# control_100.net
KiCad netlist of a schematic drawn in EAGLE
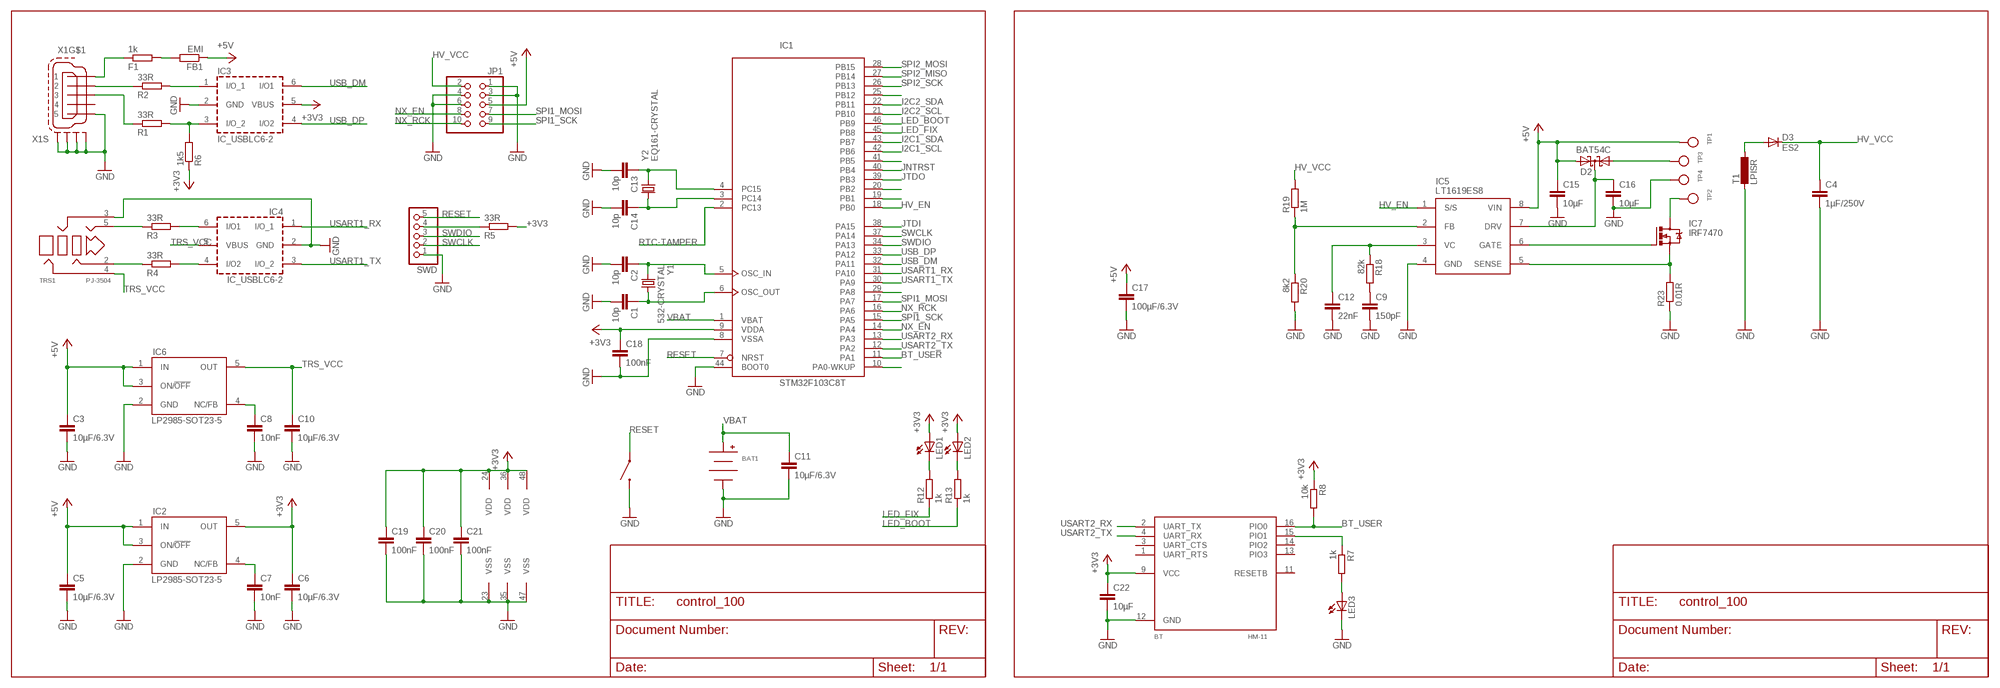
[diagram p0: schematic, sheet 1]

(export (version "E")
  (design (tool "Eeschema 10.0.6"))
  (components
    (comp (ref "BAT1")
      (value "CR1220-HOLDER")
      (footprint "eagle-import:HARWIN-CR1220")
      (libsource (lib "eagle-import") (part "CR1220-HOLDER"))
    )
    (comp (ref "BT")
      (value "HM-11")
      (footprint "eagle-import:HM-11")
      (libsource (lib "eagle-import") (part "HM-11"))
    )
    (comp (ref "C1")
      (value "10p")
      (footprint "eagle-import:C0603")
      (libsource (lib "eagle-import") (part "C-EUC0603"))
    )
    (comp (ref "C2")
      (value "10p")
      (footprint "eagle-import:C0603")
      (libsource (lib "eagle-import") (part "C-EUC0603"))
    )
    (comp (ref "C3")
      (value "10µF/6.3V")
      (footprint "eagle-import:C0603")
      (libsource (lib "eagle-import") (part "C-EUC0603"))
    )
    (comp (ref "C4")
      (value "1µF/250V")
      (footprint "eagle-import:C2220K")
      (libsource (lib "eagle-import") (part "C-EUC2220K"))
    )
    (comp (ref "C5")
      (value "10µF/6.3V")
      (footprint "eagle-import:C0603")
      (libsource (lib "eagle-import") (part "C-EUC0603"))
    )
    (comp (ref "C6")
      (value "10µF/6.3V")
      (footprint "eagle-import:C0603")
      (libsource (lib "eagle-import") (part "C-EUC0603"))
    )
    (comp (ref "C7")
      (value "10nF")
      (footprint "eagle-import:C0603")
      (libsource (lib "eagle-import") (part "C-EUC0603"))
    )
    (comp (ref "C8")
      (value "10nF")
      (footprint "eagle-import:C0603")
      (libsource (lib "eagle-import") (part "C-EUC0603"))
    )
    (comp (ref "C9")
      (value "150pF")
      (footprint "eagle-import:C0603")
      (libsource (lib "eagle-import") (part "C-EUC0603"))
    )
    (comp (ref "C10")
      (value "10µF/6.3V")
      (footprint "eagle-import:C0603")
      (libsource (lib "eagle-import") (part "C-EUC0603"))
    )
    (comp (ref "C11")
      (value "10µF/6.3V")
      (footprint "eagle-import:C0603")
      (libsource (lib "eagle-import") (part "C-EUC0603"))
    )
    (comp (ref "C12")
      (value "22nF")
      (footprint "eagle-import:C0603")
      (libsource (lib "eagle-import") (part "C-EUC0603"))
    )
    (comp (ref "C13")
      (value "10p")
      (footprint "eagle-import:C0603")
      (libsource (lib "eagle-import") (part "C-EUC0603"))
    )
    (comp (ref "C14")
      (value "10p")
      (footprint "eagle-import:C0603")
      (libsource (lib "eagle-import") (part "C-EUC0603"))
    )
    (comp (ref "C15")
      (value "10µF")
      (footprint "eagle-import:C0603")
      (libsource (lib "eagle-import") (part "C-EUC0603"))
    )
    (comp (ref "C16")
      (value "10µF")
      (footprint "eagle-import:C0603")
      (libsource (lib "eagle-import") (part "C-EUC0603"))
    )
    (comp (ref "C17")
      (value "100µF/6.3V")
      (footprint "eagle-import:C1210")
      (libsource (lib "eagle-import") (part "C-EUC1210"))
    )
    (comp (ref "C18")
      (value "100nF")
      (footprint "eagle-import:C0603")
      (libsource (lib "eagle-import") (part "C-EUC0603"))
    )
    (comp (ref "C19")
      (value "100nF")
      (footprint "eagle-import:C0603")
      (libsource (lib "eagle-import") (part "C-EUC0603"))
    )
    (comp (ref "C20")
      (value "100nF")
      (footprint "eagle-import:C0603")
      (libsource (lib "eagle-import") (part "C-EUC0603"))
    )
    (comp (ref "C21")
      (value "100nF")
      (footprint "eagle-import:C0603")
      (libsource (lib "eagle-import") (part "C-EUC0603"))
    )
    (comp (ref "C22")
      (value "10µF")
      (footprint "eagle-import:C0603")
      (libsource (lib "eagle-import") (part "C-EUC0603"))
    )
    (comp (ref "D2")
      (value "BAT54C")
      (footprint "eagle-import:SOT23")
      (libsource (lib "eagle-import") (part "BAT54C"))
    )
    (comp (ref "D3")
      (value "ES2")
      (footprint "eagle-import:DO-214AA")
      (libsource (lib "eagle-import") (part "ES2"))
    )
    (comp (ref "F1")
      (value "1k")
      (footprint "eagle-import:R0603")
      (libsource (lib "eagle-import") (part "R-EU_R0603"))
    )
    (comp (ref "FB1")
      (value "EMI")
      (footprint "eagle-import:R0603")
      (libsource (lib "eagle-import") (part "R-EU_R0603"))
    )
    (comp (ref "IC1")
      (value "STM32F103C8T")
      (footprint "eagle-import:LQFP48")
      (libsource (lib "eagle-import") (part "STM32F103CT8"))
    )
    (comp (ref "IC2")
      (value "LP2985-SOT23-5")
      (footprint "eagle-import:SOT23-5")
      (libsource (lib "eagle-import") (part "LP2985-SOT23-5"))
    )
    (comp (ref "IC3")
      (value "IC_USBLC6-2")
      (footprint "eagle-import:SOT-23-6L")
      (libsource (lib "eagle-import") (part "IC_USBLC6-2"))
    )
    (comp (ref "IC4")
      (value "IC_USBLC6-2")
      (footprint "eagle-import:SOT-23-6L")
      (libsource (lib "eagle-import") (part "IC_USBLC6-2"))
    )
    (comp (ref "IC5")
      (value "LT1619ES8")
      (footprint "eagle-import:SO8")
      (libsource (lib "eagle-import") (part "LT1619ES8"))
    )
    (comp (ref "IC6")
      (value "LP2985-SOT23-5")
      (footprint "eagle-import:SOT23-5")
      (libsource (lib "eagle-import") (part "LP2985-SOT23-5"))
    )
    (comp (ref "IC7")
      (value "IRF7470")
      (footprint "eagle-import:SO8")
      (libsource (lib "eagle-import") (part "IRF7470"))
    )
    (comp (ref "ISP")
      (value "TACT-SWITCH-40-40")
      (footprint "eagle-import:40-40")
      (libsource (lib "eagle-import") (part "TACT-SWITCH-40-40"))
    )
    (comp (ref "JP1")
      (value "PINHD-2X5_2.54-SMD")
      (footprint "eagle-import:2X05SMD")
      (libsource (lib "eagle-import") (part "PINHD-2X5_2.54-SMD"))
    )
    (comp (ref "LED1")
      (value "LEDCHIP-LED0603")
      (footprint "eagle-import:CHIP-LED0603")
      (libsource (lib "eagle-import") (part "LEDCHIP-LED0603"))
    )
    (comp (ref "LED2")
      (value "LEDCHIP-LED0603")
      (footprint "eagle-import:CHIP-LED0603")
      (libsource (lib "eagle-import") (part "LEDCHIP-LED0603"))
    )
    (comp (ref "LED3")
      (value "LEDCHIP-LED0603")
      (footprint "eagle-import:CHIP-LED0603")
      (libsource (lib "eagle-import") (part "LEDCHIP-LED0603"))
    )
    (comp (ref "R1")
      (value "33R")
      (footprint "eagle-import:R0603")
      (libsource (lib "eagle-import") (part "R-EU_R0603"))
    )
    (comp (ref "R2")
      (value "33R")
      (footprint "eagle-import:R0603")
      (libsource (lib "eagle-import") (part "R-EU_R0603"))
    )
    (comp (ref "R3")
      (value "33R")
      (footprint "eagle-import:R0603")
      (libsource (lib "eagle-import") (part "R-EU_R0603"))
    )
    (comp (ref "R4")
      (value "33R")
      (footprint "eagle-import:R0603")
      (libsource (lib "eagle-import") (part "R-EU_R0603"))
    )
    (comp (ref "R5")
      (value "33R")
      (footprint "eagle-import:R0603")
      (libsource (lib "eagle-import") (part "R-EU_R0603"))
    )
    (comp (ref "R6")
      (value "1k5")
      (footprint "eagle-import:R0603")
      (libsource (lib "eagle-import") (part "R-EU_R0603"))
    )
    (comp (ref "R7")
      (value "1k")
      (footprint "eagle-import:R0603")
      (libsource (lib "eagle-import") (part "R-EU_R0603"))
    )
    (comp (ref "R8")
      (value "10k")
      (footprint "eagle-import:R0603")
      (libsource (lib "eagle-import") (part "R-EU_R0603"))
    )
    (comp (ref "R12")
      (value "1k")
      (footprint "eagle-import:R0603")
      (libsource (lib "eagle-import") (part "R-EU_R0603"))
    )
    (comp (ref "R13")
      (value "1k")
      (footprint "eagle-import:R0603")
      (libsource (lib "eagle-import") (part "R-EU_R0603"))
    )
    (comp (ref "R18")
      (value "82k")
      (footprint "eagle-import:R0603")
      (libsource (lib "eagle-import") (part "R-EU_R0603"))
    )
    (comp (ref "R19")
      (value "1M")
      (footprint "eagle-import:M1206")
      (libsource (lib "eagle-import") (part "R-EU_M1206"))
    )
    (comp (ref "R20")
      (value "8k2")
      (footprint "eagle-import:R0603")
      (libsource (lib "eagle-import") (part "R-EU_R0603"))
    )
    (comp (ref "R23")
      (value "0.01R")
      (footprint "eagle-import:R1206")
      (libsource (lib "eagle-import") (part "R-EU_R1206"))
    )
    (comp (ref "SWD")
      (value "HEADER-1X5ROUND")
      (footprint "eagle-import:1X05_ROUND")
      (libsource (lib "eagle-import") (part "HEADER-1X5ROUND"))
    )
    (comp (ref "T1")
      (value "LPISR")
      (footprint "eagle-import:PISR")
      (libsource (lib "eagle-import") (part "LPISR"))
    )
    (comp (ref "TP1")
      (value "TESTPOINTROUND2MM")
      (footprint "eagle-import:TESTPOINT_ROUND_2MM")
      (libsource (lib "eagle-import") (part "TESTPOINTROUND2MM"))
    )
    (comp (ref "TP2")
      (value "TESTPOINTROUND2MM")
      (footprint "eagle-import:TESTPOINT_ROUND_2MM")
      (libsource (lib "eagle-import") (part "TESTPOINTROUND2MM"))
    )
    (comp (ref "TP3")
      (value "TESTPOINTROUND2MM")
      (footprint "eagle-import:TESTPOINT_ROUND_2MM")
      (libsource (lib "eagle-import") (part "TESTPOINTROUND2MM"))
    )
    (comp (ref "TP4")
      (value "TESTPOINTROUND2MM")
      (footprint "eagle-import:TESTPOINT_ROUND_2MM")
      (libsource (lib "eagle-import") (part "TESTPOINTROUND2MM"))
    )
    (comp (ref "TRS1")
      (value "PJ-3504")
      (footprint "eagle-import:YD-PJ-3504")
      (libsource (lib "eagle-import") (part "PJ-3504"))
    )
    (comp (ref "X1")
      (value "MINI-USB-SCHIELD-32005-201")
      (footprint "eagle-import:32005-201")
      (libsource (lib "eagle-import") (part "MINI-USB-SCHIELD-32005-201"))
    )
    (comp (ref "Y1")
      (value "532-CRYSTAL")
      (footprint "eagle-import:2PIN50X32")
      (libsource (lib "eagle-import") (part "532-CRYSTAL"))
    )
    (comp (ref "Y2")
      (value "EQ161-CRYSTAL")
      (footprint "eagle-import:EQ161")
      (libsource (lib "eagle-import") (part "EQ161-CRYSTAL"))
    )
  )
  (nets
    (net (code "1") (name "+3V3") (class "Default")
      (node (ref "BT") (pin "9") (pinfunction "VCC_9") (pintype "bidirectional"))
      (node (ref "C18") (pin "1") (pinfunction "1_1") (pintype "passive"))
      (node (ref "C19") (pin "1") (pinfunction "1_1") (pintype "passive"))
      (node (ref "C20") (pin "1") (pinfunction "1_1") (pintype "passive"))
      (node (ref "C21") (pin "1") (pinfunction "1_1") (pintype "passive"))
      (node (ref "C22") (pin "1") (pinfunction "1_1") (pintype "passive"))
      (node (ref "C6") (pin "1") (pinfunction "1_1") (pintype "passive"))
      (node (ref "IC1") (pin "24") (pinfunction "VDD_24") (pintype "power_in"))
      (node (ref "IC1") (pin "36") (pinfunction "VDD_36") (pintype "power_in"))
      (node (ref "IC1") (pin "48") (pinfunction "VDD_48") (pintype "power_in"))
      (node (ref "IC1") (pin "9") (pinfunction "VDDA_9") (pintype "power_in"))
      (node (ref "IC2") (pin "5") (pinfunction "OUT_5") (pintype "bidirectional"))
      (node (ref "IC3") (pin "5") (pinfunction "VBUS_5") (pintype "bidirectional"))
      (node (ref "LED1") (pin "A") (pinfunction "A_A") (pintype "passive"))
      (node (ref "LED2") (pin "A") (pinfunction "A_A") (pintype "passive"))
      (node (ref "R5") (pin "2") (pinfunction "2_2") (pintype "passive"))
      (node (ref "R6") (pin "1") (pinfunction "1_1") (pintype "passive"))
      (node (ref "R8") (pin "1") (pinfunction "1_1") (pintype "passive"))
    )
    (net (code "2") (name "+5V") (class "Default")
      (node (ref "C15") (pin "1") (pinfunction "1_1") (pintype "passive"))
      (node (ref "C17") (pin "1") (pinfunction "1_1") (pintype "passive"))
      (node (ref "C3") (pin "1") (pinfunction "1_1") (pintype "passive"))
      (node (ref "C5") (pin "1") (pinfunction "1_1") (pintype "passive"))
      (node (ref "D2") (pin "2") (pinfunction "A2_2") (pintype "passive"))
      (node (ref "FB1") (pin "1") (pinfunction "1_1") (pintype "passive"))
      (node (ref "IC2") (pin "1") (pinfunction "IN_1") (pintype "bidirectional"))
      (node (ref "IC2") (pin "3") (pinfunction "ON/~{OFF}_3") (pintype "bidirectional"))
      (node (ref "IC5") (pin "8") (pinfunction "VIN_8") (pintype "bidirectional"))
      (node (ref "IC6") (pin "1") (pinfunction "IN_1") (pintype "bidirectional"))
      (node (ref "IC6") (pin "3") (pinfunction "ON/~{OFF}_3") (pintype "bidirectional"))
      (node (ref "JP1") (pin "5") (pinfunction "5_5") (pintype "passive"))
      (node (ref "TP1") (pin "P$1") (pinfunction "P$1_P$1") (pintype "bidirectional"))
    )
    (net (code "3") (name "/BT_USER") (class "Default")
      (node (ref "BT") (pin "16") (pinfunction "PIO0_16") (pintype "bidirectional"))
      (node (ref "IC1") (pin "11") (pinfunction "PA1_11") (pintype "bidirectional"))
      (node (ref "R8") (pin "2") (pinfunction "2_2") (pintype "passive"))
    )
    (net (code "4") (name "/HV_EN") (class "Default")
      (node (ref "IC1") (pin "18") (pinfunction "PB0_18") (pintype "bidirectional"))
      (node (ref "IC5") (pin "1") (pinfunction "S/S_1") (pintype "bidirectional"))
    )
    (net (code "5") (name "/HV_VCC") (class "Default")
      (node (ref "C4") (pin "1") (pinfunction "1_1") (pintype "passive"))
      (node (ref "D3") (pin "C") (pinfunction "C_C") (pintype "passive"))
      (node (ref "JP1") (pin "2") (pinfunction "2_2") (pintype "passive"))
      (node (ref "R19") (pin "2") (pinfunction "2_2") (pintype "passive"))
    )
    (net (code "6") (name "/I2C1_SCL") (class "Default")
      (node (ref "IC1") (pin "42") (pinfunction "PB6_42") (pintype "bidirectional"))
    )
    (net (code "7") (name "/I2C1_SDA") (class "Default")
      (node (ref "IC1") (pin "43") (pinfunction "PB7_43") (pintype "bidirectional"))
    )
    (net (code "8") (name "/I2C2_SCL") (class "Default")
      (node (ref "IC1") (pin "21") (pinfunction "PB10_21") (pintype "bidirectional"))
    )
    (net (code "9") (name "/I2C2_SDA") (class "Default")
      (node (ref "IC1") (pin "22") (pinfunction "PB11_22") (pintype "bidirectional"))
    )
    (net (code "10") (name "/JNTRST") (class "Default")
      (node (ref "IC1") (pin "40") (pinfunction "PB4_40") (pintype "bidirectional"))
    )
    (net (code "11") (name "/JTDI") (class "Default")
      (node (ref "IC1") (pin "38") (pinfunction "PA15_38") (pintype "bidirectional"))
    )
    (net (code "12") (name "/JTDO") (class "Default")
      (node (ref "IC1") (pin "39") (pinfunction "PB3_39") (pintype "bidirectional"))
    )
    (net (code "13") (name "/LED_BOOT") (class "Default")
      (node (ref "IC1") (pin "46") (pinfunction "PB9_46") (pintype "bidirectional"))
      (node (ref "R13") (pin "1") (pinfunction "1_1") (pintype "passive"))
    )
    (net (code "14") (name "/LED_FIX") (class "Default")
      (node (ref "IC1") (pin "45") (pinfunction "PB8_45") (pintype "bidirectional"))
      (node (ref "R12") (pin "1") (pinfunction "1_1") (pintype "passive"))
    )
    (net (code "15") (name "/NX_EN") (class "Default")
      (node (ref "IC1") (pin "14") (pinfunction "PA4_14") (pintype "bidirectional"))
      (node (ref "JP1") (pin "8") (pinfunction "8_8") (pintype "passive"))
    )
    (net (code "16") (name "/NX_RCK") (class "Default")
      (node (ref "IC1") (pin "16") (pinfunction "PA6_16") (pintype "bidirectional"))
      (node (ref "JP1") (pin "10") (pinfunction "10_10") (pintype "passive"))
    )
    (net (code "17") (name "/RESET") (class "Default")
      (node (ref "IC1") (pin "7") (pinfunction "NRST_7") (pintype "bidirectional"))
      (node (ref "ISP") (pin "3") (pinfunction "P$2_3") (pintype "bidirectional"))
      (node (ref "ISP") (pin "4") (pinfunction "P$2_4") (pintype "bidirectional"))
      (node (ref "SWD") (pin "5") (pinfunction "5_5") (pintype "passive"))
    )
    (net (code "18") (name "/RTC-TAMPER") (class "Default")
      (node (ref "IC1") (pin "2") (pinfunction "PC13_2") (pintype "bidirectional"))
    )
    (net (code "19") (name "/SPI1_MOSI") (class "Default")
      (node (ref "IC1") (pin "17") (pinfunction "PA7_17") (pintype "bidirectional"))
      (node (ref "JP1") (pin "7") (pinfunction "7_7") (pintype "passive"))
    )
    (net (code "20") (name "/SPI1_SCK") (class "Default")
      (node (ref "IC1") (pin "15") (pinfunction "PA5_15") (pintype "bidirectional"))
      (node (ref "JP1") (pin "9") (pinfunction "9_9") (pintype "passive"))
    )
    (net (code "21") (name "/SPI2_MISO") (class "Default")
      (node (ref "IC1") (pin "27") (pinfunction "PB14_27") (pintype "bidirectional"))
    )
    (net (code "22") (name "/SPI2_MOSI") (class "Default")
      (node (ref "IC1") (pin "28") (pinfunction "PB15_28") (pintype "bidirectional"))
    )
    (net (code "23") (name "/SPI2_SCK") (class "Default")
      (node (ref "IC1") (pin "26") (pinfunction "PB13_26") (pintype "bidirectional"))
    )
    (net (code "24") (name "/SWCLK") (class "Default")
      (node (ref "IC1") (pin "37") (pinfunction "PA14_37") (pintype "bidirectional"))
      (node (ref "SWD") (pin "2") (pinfunction "2_2") (pintype "passive"))
    )
    (net (code "25") (name "/SWDIO") (class "Default")
      (node (ref "IC1") (pin "34") (pinfunction "PA13_34") (pintype "bidirectional"))
      (node (ref "SWD") (pin "3") (pinfunction "3_3") (pintype "passive"))
    )
    (net (code "26") (name "/TRS_VCC") (class "Default")
      (node (ref "C10") (pin "1") (pinfunction "1_1") (pintype "passive"))
      (node (ref "IC4") (pin "5") (pinfunction "VBUS_5") (pintype "bidirectional"))
      (node (ref "IC6") (pin "5") (pinfunction "OUT_5") (pintype "bidirectional"))
      (node (ref "TRS1") (pin "4") (pinfunction "4_4") (pintype "bidirectional"))
    )
    (net (code "27") (name "/USART1_RX") (class "Default")
      (node (ref "IC1") (pin "31") (pinfunction "PA10_31") (pintype "bidirectional"))
      (node (ref "IC4") (pin "1") (pinfunction "I/O_1_1") (pintype "bidirectional"))
    )
    (net (code "28") (name "/USART1_TX") (class "Default")
      (node (ref "IC1") (pin "30") (pinfunction "PA9_30") (pintype "bidirectional"))
      (node (ref "IC4") (pin "3") (pinfunction "I/O_2_3") (pintype "bidirectional"))
    )
    (net (code "29") (name "/USART2_RX") (class "Default")
      (node (ref "BT") (pin "2") (pinfunction "UART_TX_2") (pintype "bidirectional"))
      (node (ref "IC1") (pin "13") (pinfunction "PA3_13") (pintype "bidirectional"))
    )
    (net (code "30") (name "/USART2_TX") (class "Default")
      (node (ref "BT") (pin "4") (pinfunction "UART_RX_4") (pintype "bidirectional"))
      (node (ref "IC1") (pin "12") (pinfunction "PA2_12") (pintype "bidirectional"))
    )
    (net (code "31") (name "/USB_DM") (class "Default")
      (node (ref "IC1") (pin "32") (pinfunction "PA11_32") (pintype "bidirectional"))
      (node (ref "IC3") (pin "6") (pinfunction "I/O1_6") (pintype "bidirectional"))
    )
    (net (code "32") (name "/USB_DP") (class "Default")
      (node (ref "IC1") (pin "33") (pinfunction "PA12_33") (pintype "bidirectional"))
      (node (ref "IC3") (pin "4") (pinfunction "I/O2_4") (pintype "bidirectional"))
    )
    (net (code "33") (name "/VBAT") (class "Default")
      (node (ref "BAT1") (pin "POS") (pinfunction "POS_POS") (pintype "bidirectional"))
      (node (ref "C11") (pin "1") (pinfunction "1_1") (pintype "passive"))
      (node (ref "IC1") (pin "1") (pinfunction "VBAT_1") (pintype "power_in"))
    )
    (net (code "34") (name "GND") (class "Default")
      (node (ref "BAT1") (pin "NEG") (pinfunction "NEG_NEG") (pintype "bidirectional"))
      (node (ref "BT") (pin "12") (pinfunction "GND_12") (pintype "bidirectional"))
      (node (ref "C1") (pin "2") (pinfunction "2_2") (pintype "passive"))
      (node (ref "C10") (pin "2") (pinfunction "2_2") (pintype "passive"))
      (node (ref "C11") (pin "2") (pinfunction "2_2") (pintype "passive"))
      (node (ref "C12") (pin "2") (pinfunction "2_2") (pintype "passive"))
      (node (ref "C13") (pin "2") (pinfunction "2_2") (pintype "passive"))
      (node (ref "C14") (pin "2") (pinfunction "2_2") (pintype "passive"))
      (node (ref "C15") (pin "2") (pinfunction "2_2") (pintype "passive"))
      (node (ref "C16") (pin "2") (pinfunction "2_2") (pintype "passive"))
      (node (ref "C17") (pin "2") (pinfunction "2_2") (pintype "passive"))
      (node (ref "C18") (pin "2") (pinfunction "2_2") (pintype "passive"))
      (node (ref "C19") (pin "2") (pinfunction "2_2") (pintype "passive"))
      (node (ref "C2") (pin "2") (pinfunction "2_2") (pintype "passive"))
      (node (ref "C20") (pin "2") (pinfunction "2_2") (pintype "passive"))
      (node (ref "C21") (pin "2") (pinfunction "2_2") (pintype "passive"))
      (node (ref "C22") (pin "2") (pinfunction "2_2") (pintype "passive"))
      (node (ref "C3") (pin "2") (pinfunction "2_2") (pintype "passive"))
      (node (ref "C4") (pin "2") (pinfunction "2_2") (pintype "passive"))
      (node (ref "C5") (pin "2") (pinfunction "2_2") (pintype "passive"))
      (node (ref "C6") (pin "2") (pinfunction "2_2") (pintype "passive"))
      (node (ref "C7") (pin "2") (pinfunction "2_2") (pintype "passive"))
      (node (ref "C8") (pin "2") (pinfunction "2_2") (pintype "passive"))
      (node (ref "C9") (pin "2") (pinfunction "2_2") (pintype "passive"))
      (node (ref "IC1") (pin "23") (pinfunction "VSS_23") (pintype "power_in"))
      (node (ref "IC1") (pin "35") (pinfunction "VSS_35") (pintype "power_in"))
      (node (ref "IC1") (pin "44") (pinfunction "BOOT0_44") (pintype "input"))
      (node (ref "IC1") (pin "47") (pinfunction "VSS_47") (pintype "power_in"))
      (node (ref "IC1") (pin "8") (pinfunction "VSSA_8") (pintype "power_in"))
      (node (ref "IC2") (pin "2") (pinfunction "GND_2") (pintype "bidirectional"))
      (node (ref "IC3") (pin "2") (pinfunction "GND_2") (pintype "bidirectional"))
      (node (ref "IC4") (pin "2") (pinfunction "GND_2") (pintype "bidirectional"))
      (node (ref "IC5") (pin "4") (pinfunction "GND_4") (pintype "bidirectional"))
      (node (ref "IC6") (pin "2") (pinfunction "GND_2") (pintype "bidirectional"))
      (node (ref "ISP") (pin "1") (pinfunction "P$1_1") (pintype "bidirectional"))
      (node (ref "ISP") (pin "2") (pinfunction "P$1_2") (pintype "bidirectional"))
      (node (ref "JP1") (pin "1") (pinfunction "1_1") (pintype "passive"))
      (node (ref "JP1") (pin "3") (pinfunction "3_3") (pintype "passive"))
      (node (ref "JP1") (pin "4") (pinfunction "4_4") (pintype "passive"))
      (node (ref "JP1") (pin "6") (pinfunction "6_6") (pintype "passive"))
      (node (ref "LED3") (pin "C") (pinfunction "C_C") (pintype "passive"))
      (node (ref "R20") (pin "2") (pinfunction "2_2") (pintype "passive"))
      (node (ref "R23") (pin "1") (pinfunction "1_1") (pintype "passive"))
      (node (ref "SWD") (pin "1") (pinfunction "1_1") (pintype "passive"))
      (node (ref "T1") (pin "P$2") (pinfunction "2_P$2") (pintype "passive"))
      (node (ref "TP4") (pin "P$1") (pinfunction "P$1_P$1") (pintype "bidirectional"))
      (node (ref "TRS1") (pin "3") (pinfunction "3_3") (pintype "bidirectional"))
      (node (ref "X1") (pin "5") (pinfunction "5_5") (pintype "passive"))
      (node (ref "X1") (pin "M1") (pinfunction "S1_M1") (pintype "passive"))
      (node (ref "X1") (pin "M2") (pinfunction "S2_M2") (pintype "passive"))
      (node (ref "X1") (pin "M3") (pinfunction "S3_M3") (pintype "passive"))
      (node (ref "X1") (pin "M4") (pinfunction "S4_M4") (pintype "passive"))
    )
    (net (code "35") (name "Net-(BT-PIO1)") (class "Default")
      (node (ref "BT") (pin "15") (pinfunction "PIO1_15") (pintype "bidirectional"))
      (node (ref "R7") (pin "1") (pinfunction "1_1") (pintype "passive"))
    )
    (net (code "36") (name "Net-(C9-Pad1)") (class "Default")
      (node (ref "C9") (pin "1") (pinfunction "1_1") (pintype "passive"))
      (node (ref "R18") (pin "2") (pinfunction "2_2") (pintype "passive"))
    )
    (net (code "37") (name "Net-(D2-A1)") (class "Default")
      (node (ref "D2") (pin "1") (pinfunction "A1_1") (pintype "passive"))
      (node (ref "TP3") (pin "P$1") (pinfunction "P$1_P$1") (pintype "bidirectional"))
    )
    (net (code "38") (name "Net-(D2-CC)") (class "Default")
      (node (ref "C16") (pin "1") (pinfunction "1_1") (pintype "passive"))
      (node (ref "D2") (pin "3") (pinfunction "CC_3") (pintype "passive"))
      (node (ref "IC5") (pin "7") (pinfunction "DRV_7") (pintype "bidirectional"))
    )
    (net (code "39") (name "Net-(F1-Pad1)") (class "Default")
      (node (ref "F1") (pin "1") (pinfunction "1_1") (pintype "passive"))
      (node (ref "X1") (pin "1") (pinfunction "1_1") (pintype "passive"))
    )
    (net (code "40") (name "Net-(F1-Pad2)") (class "Default")
      (node (ref "F1") (pin "2") (pinfunction "2_2") (pintype "passive"))
      (node (ref "FB1") (pin "2") (pinfunction "2_2") (pintype "passive"))
    )
    (net (code "41") (name "Net-(IC1A-OSC_IN)") (class "Default")
      (node (ref "C2") (pin "1") (pinfunction "1_1") (pintype "passive"))
      (node (ref "IC1") (pin "5") (pinfunction "OSC_IN_5") (pintype "bidirectional"))
      (node (ref "Y1") (pin "P$2") (pinfunction "2_P$2") (pintype "passive"))
    )
    (net (code "42") (name "Net-(IC1A-OSC_OUT)") (class "Default")
      (node (ref "C1") (pin "1") (pinfunction "1_1") (pintype "passive"))
      (node (ref "IC1") (pin "6") (pinfunction "OSC_OUT_6") (pintype "bidirectional"))
      (node (ref "Y1") (pin "P$1") (pinfunction "1_P$1") (pintype "passive"))
    )
    (net (code "43") (name "Net-(IC1A-PC14)") (class "Default")
      (node (ref "C14") (pin "1") (pinfunction "1_1") (pintype "passive"))
      (node (ref "IC1") (pin "3") (pinfunction "PC14_3") (pintype "bidirectional"))
      (node (ref "Y2") (pin "P$2") (pinfunction "2_P$2") (pintype "passive"))
    )
    (net (code "44") (name "Net-(IC1A-PC15)") (class "Default")
      (node (ref "C13") (pin "1") (pinfunction "1_1") (pintype "passive"))
      (node (ref "IC1") (pin "4") (pinfunction "PC15_4") (pintype "bidirectional"))
      (node (ref "Y2") (pin "P$1") (pinfunction "1_P$1") (pintype "passive"))
    )
    (net (code "45") (name "Net-(IC2-NC{slash}FB)") (class "Default")
      (node (ref "C7") (pin "1") (pinfunction "1_1") (pintype "passive"))
      (node (ref "IC2") (pin "4") (pinfunction "NC/FB_4") (pintype "bidirectional"))
    )
    (net (code "46") (name "Net-(IC3-I{slash}O_1)") (class "Default")
      (node (ref "IC3") (pin "1") (pinfunction "I/O_1_1") (pintype "bidirectional"))
      (node (ref "R2") (pin "2") (pinfunction "2_2") (pintype "passive"))
    )
    (net (code "47") (name "Net-(IC3-I{slash}O_2)") (class "Default")
      (node (ref "IC3") (pin "3") (pinfunction "I/O_2_3") (pintype "bidirectional"))
      (node (ref "R1") (pin "2") (pinfunction "2_2") (pintype "passive"))
      (node (ref "R6") (pin "2") (pinfunction "2_2") (pintype "passive"))
    )
    (net (code "48") (name "Net-(IC4-I{slash}O1)") (class "Default")
      (node (ref "IC4") (pin "6") (pinfunction "I/O1_6") (pintype "bidirectional"))
      (node (ref "R3") (pin "2") (pinfunction "2_2") (pintype "passive"))
    )
    (net (code "49") (name "Net-(IC4-I{slash}O2)") (class "Default")
      (node (ref "IC4") (pin "4") (pinfunction "I/O2_4") (pintype "bidirectional"))
      (node (ref "R4") (pin "2") (pinfunction "2_2") (pintype "passive"))
    )
    (net (code "50") (name "Net-(IC5-FB)") (class "Default")
      (node (ref "IC5") (pin "2") (pinfunction "FB_2") (pintype "bidirectional"))
      (node (ref "R19") (pin "1") (pinfunction "1_1") (pintype "passive"))
      (node (ref "R20") (pin "1") (pinfunction "1_1") (pintype "passive"))
    )
    (net (code "51") (name "Net-(IC5-GATE)") (class "Default")
      (node (ref "IC5") (pin "6") (pinfunction "GATE_6") (pintype "bidirectional"))
      (node (ref "IC7") (pin "4") (pinfunction "G_4") (pintype "passive"))
    )
    (net (code "52") (name "Net-(IC5-SENSE)") (class "Default")
      (node (ref "IC5") (pin "5") (pinfunction "SENSE_5") (pintype "bidirectional"))
      (node (ref "IC7") (pin "1") (pinfunction "S_1") (pintype "passive"))
      (node (ref "IC7") (pin "2") (pinfunction "S_2") (pintype "passive"))
      (node (ref "IC7") (pin "3") (pinfunction "S_3") (pintype "passive"))
      (node (ref "R23") (pin "2") (pinfunction "2_2") (pintype "passive"))
    )
    (net (code "53") (name "Net-(IC5-VC)") (class "Default")
      (node (ref "C12") (pin "1") (pinfunction "1_1") (pintype "passive"))
      (node (ref "IC5") (pin "3") (pinfunction "VC_3") (pintype "bidirectional"))
      (node (ref "R18") (pin "1") (pinfunction "1_1") (pintype "passive"))
    )
    (net (code "54") (name "Net-(IC6-NC{slash}FB)") (class "Default")
      (node (ref "C8") (pin "1") (pinfunction "1_1") (pintype "passive"))
      (node (ref "IC6") (pin "4") (pinfunction "NC/FB_4") (pintype "bidirectional"))
    )
    (net (code "55") (name "Net-(IC7-D-Pad5)") (class "Default")
      (node (ref "IC7") (pin "5") (pinfunction "D_5") (pintype "passive"))
      (node (ref "IC7") (pin "6") (pinfunction "D_6") (pintype "passive"))
      (node (ref "IC7") (pin "7") (pinfunction "D_7") (pintype "passive"))
      (node (ref "IC7") (pin "8") (pinfunction "D_8") (pintype "passive"))
      (node (ref "TP2") (pin "P$1") (pinfunction "P$1_P$1") (pintype "bidirectional"))
    )
    (net (code "56") (name "Net-(LED1-PadC)") (class "Default")
      (node (ref "LED1") (pin "C") (pinfunction "C_C") (pintype "passive"))
      (node (ref "R12") (pin "2") (pinfunction "2_2") (pintype "passive"))
    )
    (net (code "57") (name "Net-(LED2-PadC)") (class "Default")
      (node (ref "LED2") (pin "C") (pinfunction "C_C") (pintype "passive"))
      (node (ref "R13") (pin "2") (pinfunction "2_2") (pintype "passive"))
    )
    (net (code "58") (name "Net-(LED3-PadA)") (class "Default")
      (node (ref "LED3") (pin "A") (pinfunction "A_A") (pintype "passive"))
      (node (ref "R7") (pin "2") (pinfunction "2_2") (pintype "passive"))
    )
    (net (code "59") (name "Net-(R1-Pad1)") (class "Default")
      (node (ref "R1") (pin "1") (pinfunction "1_1") (pintype "passive"))
      (node (ref "X1") (pin "3") (pinfunction "3_3") (pintype "passive"))
    )
    (net (code "60") (name "Net-(R2-Pad1)") (class "Default")
      (node (ref "R2") (pin "1") (pinfunction "1_1") (pintype "passive"))
      (node (ref "X1") (pin "2") (pinfunction "2_2") (pintype "passive"))
    )
    (net (code "61") (name "Net-(R3-Pad1)") (class "Default")
      (node (ref "R3") (pin "1") (pinfunction "1_1") (pintype "passive"))
      (node (ref "TRS1") (pin "5") (pinfunction "5_5") (pintype "bidirectional"))
    )
    (net (code "62") (name "Net-(R4-Pad1)") (class "Default")
      (node (ref "R4") (pin "1") (pinfunction "1_1") (pintype "passive"))
      (node (ref "TRS1") (pin "2") (pinfunction "2_2") (pintype "bidirectional"))
    )
    (net (code "63") (name "Net-(R5-Pad1)") (class "Default")
      (node (ref "R5") (pin "1") (pinfunction "1_1") (pintype "passive"))
      (node (ref "SWD") (pin "4") (pinfunction "4_4") (pintype "passive"))
    )
    (net (code "64") (name "Net-(T1-1)") (class "Default")
      (node (ref "D3") (pin "A") (pinfunction "A_A") (pintype "passive"))
      (node (ref "T1") (pin "P$1") (pinfunction "1_P$1") (pintype "passive"))
    )
    (net (code "65") (name "unconnected-(BT-PIO2-Pad14)") (class "Default")
      (node (ref "BT") (pin "14") (pinfunction "PIO2_14") (pintype "bidirectional"))
    )
    (net (code "66") (name "unconnected-(BT-PIO3-Pad13)") (class "Default")
      (node (ref "BT") (pin "13") (pinfunction "PIO3_13") (pintype "bidirectional"))
    )
    (net (code "67") (name "unconnected-(BT-RESETB-Pad11)") (class "Default")
      (node (ref "BT") (pin "11") (pinfunction "RESETB_11") (pintype "bidirectional"))
    )
    (net (code "68") (name "unconnected-(BT-UART_CTS-Pad3)") (class "Default")
      (node (ref "BT") (pin "3") (pinfunction "UART_CTS_3") (pintype "bidirectional"))
    )
    (net (code "69") (name "unconnected-(BT-UART_RTS-Pad1)") (class "Default")
      (node (ref "BT") (pin "1") (pinfunction "UART_RTS_1") (pintype "bidirectional"))
    )
    (net (code "70") (name "unconnected-(IC1A-PA0-WKUP-Pad10)") (class "Default")
      (node (ref "IC1") (pin "10") (pinfunction "PA0-WKUP_10") (pintype "bidirectional"))
    )
    (net (code "71") (name "unconnected-(IC1A-PA8-Pad29)") (class "Default")
      (node (ref "IC1") (pin "29") (pinfunction "PA8_29") (pintype "bidirectional"))
    )
    (net (code "72") (name "unconnected-(IC1A-PB1-Pad19)") (class "Default")
      (node (ref "IC1") (pin "19") (pinfunction "PB1_19") (pintype "bidirectional"))
    )
    (net (code "73") (name "unconnected-(IC1A-PB2-Pad20)") (class "Default")
      (node (ref "IC1") (pin "20") (pinfunction "PB2_20") (pintype "bidirectional"))
    )
    (net (code "74") (name "unconnected-(IC1A-PB5-Pad41)") (class "Default")
      (node (ref "IC1") (pin "41") (pinfunction "PB5_41") (pintype "bidirectional"))
    )
    (net (code "75") (name "unconnected-(IC1A-PB12-Pad25)") (class "Default")
      (node (ref "IC1") (pin "25") (pinfunction "PB12_25") (pintype "bidirectional"))
    )
    (net (code "76") (name "unconnected-(X1-Pad4)") (class "Default")
      (node (ref "X1") (pin "4") (pinfunction "4_4") (pintype "passive"))
    )
  )
)
